# S6_Solenoid_Valve_Interlock.net
KiCad netlist of a schematic drawn in Altium Designer
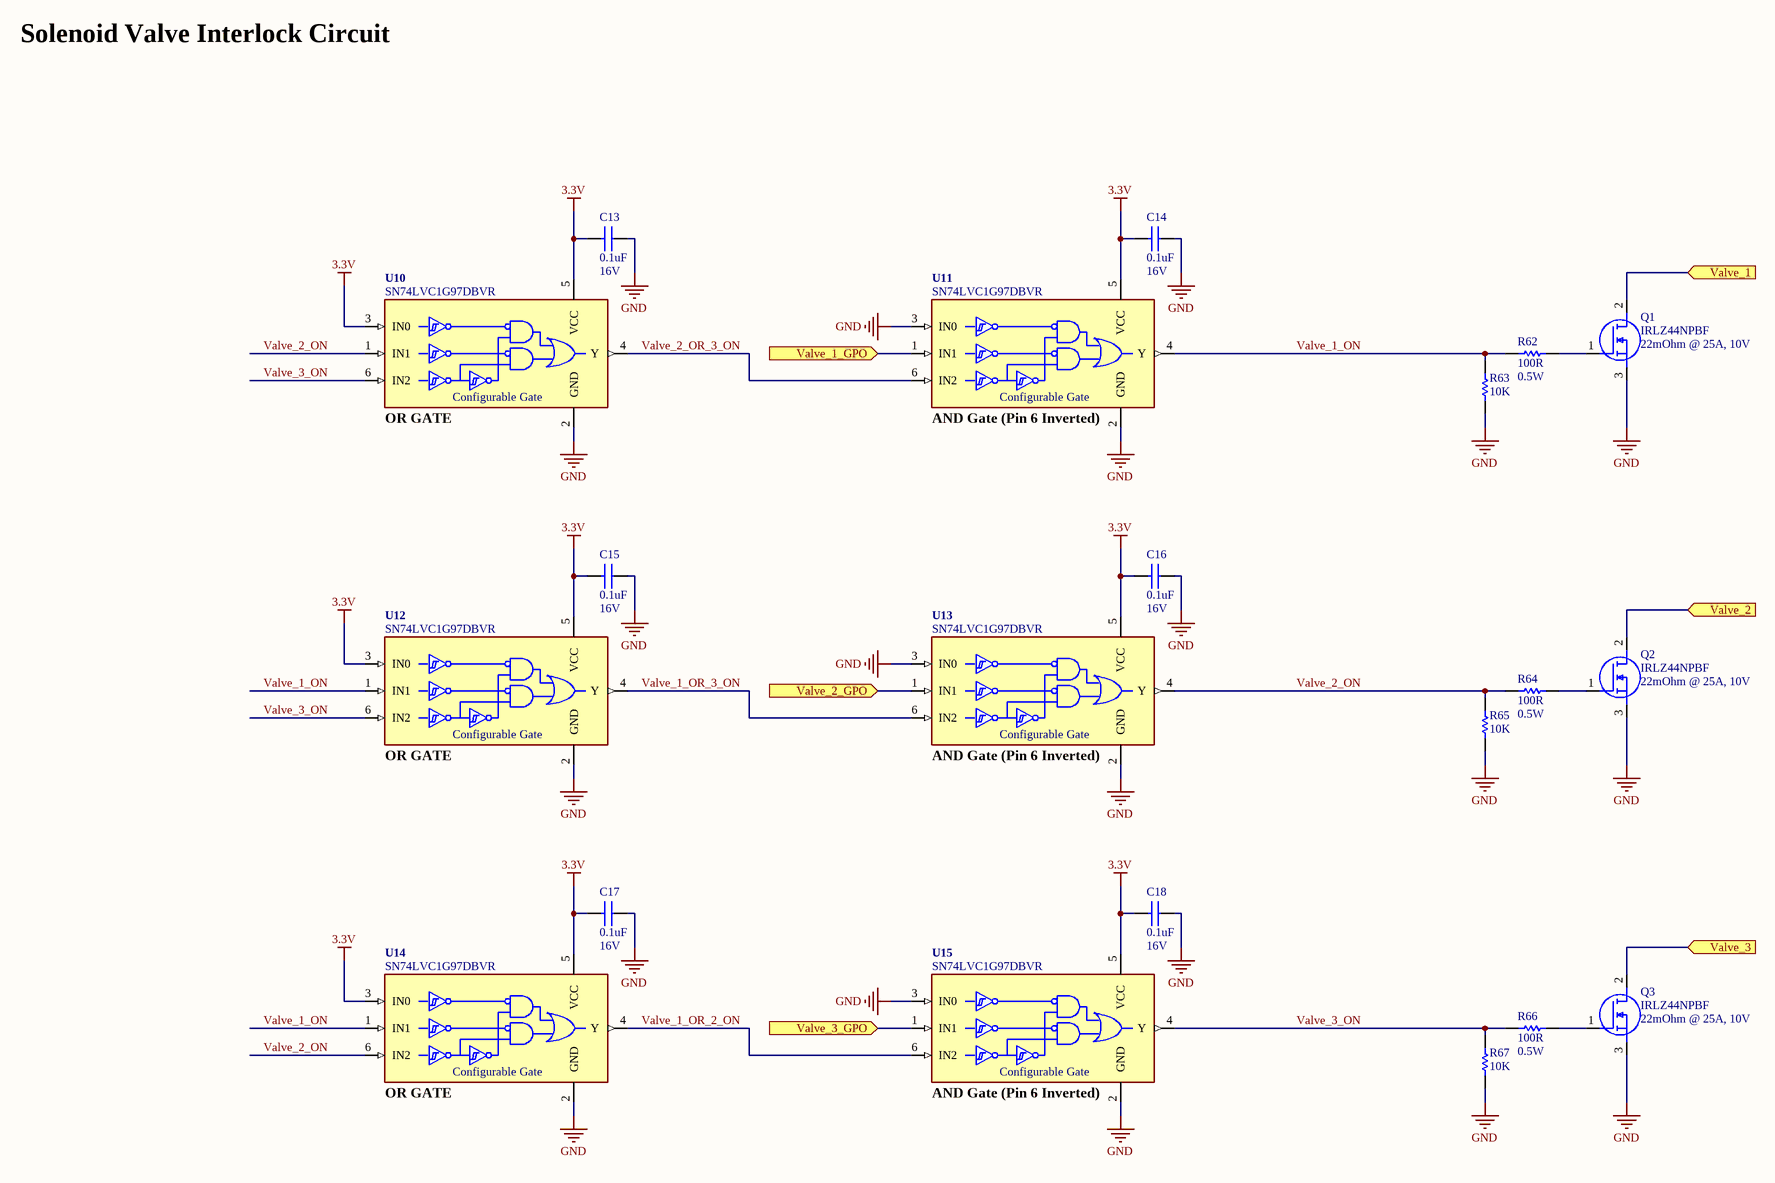
[diagram p0: S6_Solenoid_Valve_Interlock.SchDoc]

(export (version "E")
  (design (tool "Eeschema 10.0.6"))
  (components
    (comp (ref "C13")
      (value "0.1uF")
      (footprint "RWMN:CAPC1608X09N")
      (description "CAP CER 0.1UF 16V X7R 0603")
      (fields
        (field (name "MFG") "KEMET")
        (field (name "MFG_PART_NO") "C0603C104M4RACTU")
        (field (name "VOLTAGE") "16V")
      )
      (libsource (lib "AquaDrone") (part "CAP CER 0.1UF 16V X7R 0603"))
    )
    (comp (ref "C14")
      (value "0.1uF")
      (footprint "RWMN:CAPC1608X09N")
      (description "CAP CER 0.1UF 16V X7R 0603")
      (fields
        (field (name "MFG") "KEMET")
        (field (name "MFG_PART_NO") "C0603C104M4RACTU")
        (field (name "VOLTAGE") "16V")
      )
      (libsource (lib "AquaDrone") (part "CAP CER 0.1UF 16V X7R 0603"))
    )
    (comp (ref "C15")
      (value "0.1uF")
      (footprint "RWMN:CAPC1608X09N")
      (description "CAP CER 0.1UF 16V X7R 0603")
      (fields
        (field (name "MFG") "KEMET")
        (field (name "MFG_PART_NO") "C0603C104M4RACTU")
        (field (name "VOLTAGE") "16V")
      )
      (libsource (lib "AquaDrone") (part "CAP CER 0.1UF 16V X7R 0603"))
    )
    (comp (ref "C16")
      (value "0.1uF")
      (footprint "RWMN:CAPC1608X09N")
      (description "CAP CER 0.1UF 16V X7R 0603")
      (fields
        (field (name "MFG") "KEMET")
        (field (name "MFG_PART_NO") "C0603C104M4RACTU")
        (field (name "VOLTAGE") "16V")
      )
      (libsource (lib "AquaDrone") (part "CAP CER 0.1UF 16V X7R 0603"))
    )
    (comp (ref "C17")
      (value "0.1uF")
      (footprint "RWMN:CAPC1608X09N")
      (description "CAP CER 0.1UF 16V X7R 0603")
      (fields
        (field (name "MFG") "KEMET")
        (field (name "MFG_PART_NO") "C0603C104M4RACTU")
        (field (name "VOLTAGE") "16V")
      )
      (libsource (lib "AquaDrone") (part "CAP CER 0.1UF 16V X7R 0603"))
    )
    (comp (ref "C18")
      (value "0.1uF")
      (footprint "RWMN:CAPC1608X09N")
      (description "CAP CER 0.1UF 16V X7R 0603")
      (fields
        (field (name "MFG") "KEMET")
        (field (name "MFG_PART_NO") "C0603C104M4RACTU")
        (field (name "VOLTAGE") "16V")
      )
      (libsource (lib "AquaDrone") (part "CAP CER 0.1UF 16V X7R 0603"))
    )
    (comp (ref "Q1")
      (value "22mOhm @ 25A, 10V")
      (footprint "TO254P469X1042X1967-3P")
      (description "MOSFET N-CH 55V 47A TO-220AB")
      (fields (field (name "MFG") "Infineon Technologies") (field (name "MFG_PART_NO") "IRLZ44NPBF"))
      (libsource (lib "AquaDrone") (part "MOSFET N-CH 55V 47A TO-220AB"))
    )
    (comp (ref "Q2")
      (value "22mOhm @ 25A, 10V")
      (footprint "TO254P469X1042X1967-3P")
      (description "MOSFET N-CH 55V 47A TO-220AB")
      (fields (field (name "MFG") "Infineon Technologies") (field (name "MFG_PART_NO") "IRLZ44NPBF"))
      (libsource (lib "AquaDrone") (part "MOSFET N-CH 55V 47A TO-220AB"))
    )
    (comp (ref "Q3")
      (value "22mOhm @ 25A, 10V")
      (footprint "TO254P469X1042X1967-3P")
      (description "MOSFET N-CH 55V 47A TO-220AB")
      (fields (field (name "MFG") "Infineon Technologies") (field (name "MFG_PART_NO") "IRLZ44NPBF"))
      (libsource (lib "AquaDrone") (part "MOSFET N-CH 55V 47A TO-220AB"))
    )
    (comp (ref "R62")
      (value "100R")
      (footprint "RWMN:RESC3116X06N")
      (description "RES 100 OHM 1% 1/2W 1206")
      (fields
        (field (name "MFG") "Stackpole Electronics Inc")
        (field (name "MFG_PART_NO") "RNCP1206FTD100R")
        (field (name "POWER") "0.5W")
      )
      (libsource (lib "AquaDrone") (part "RES 100 OHM 1% 1/2W 1206"))
    )
    (comp (ref "R63")
      (value "10K")
      (footprint "RESC1608X06N")
      (description "RES SMD 10K OHM 1% 1/10W 0603")
      (fields (field (name "MFG") "Vishay Dale") (field (name "MFG_PART_NO") "CRCW060310K0FKEA"))
      (libsource (lib "AquaDrone") (part "RES SMD 10K OHM 1% 1/10W 0603"))
    )
    (comp (ref "R64")
      (value "100R")
      (footprint "RWMN:RESC3116X06N")
      (description "RES 100 OHM 1% 1/2W 1206")
      (fields
        (field (name "MFG") "Stackpole Electronics Inc")
        (field (name "MFG_PART_NO") "RNCP1206FTD100R")
        (field (name "POWER") "0.5W")
      )
      (libsource (lib "AquaDrone") (part "RES 100 OHM 1% 1/2W 1206"))
    )
    (comp (ref "R65")
      (value "10K")
      (footprint "RESC1608X06N")
      (description "RES SMD 10K OHM 1% 1/10W 0603")
      (fields (field (name "MFG") "Vishay Dale") (field (name "MFG_PART_NO") "CRCW060310K0FKEA"))
      (libsource (lib "AquaDrone") (part "RES SMD 10K OHM 1% 1/10W 0603"))
    )
    (comp (ref "R66")
      (value "100R")
      (footprint "RWMN:RESC3116X06N")
      (description "RES 100 OHM 1% 1/2W 1206")
      (fields
        (field (name "MFG") "Stackpole Electronics Inc")
        (field (name "MFG_PART_NO") "RNCP1206FTD100R")
        (field (name "POWER") "0.5W")
      )
      (libsource (lib "AquaDrone") (part "RES 100 OHM 1% 1/2W 1206"))
    )
    (comp (ref "R67")
      (value "10K")
      (footprint "RESC1608X06N")
      (description "RES SMD 10K OHM 1% 1/10W 0603")
      (fields (field (name "MFG") "Vishay Dale") (field (name "MFG_PART_NO") "CRCW060310K0FKEA"))
      (libsource (lib "AquaDrone") (part "RES SMD 10K OHM 1% 1/10W 0603"))
    )
    (comp (ref "U10")
      (value "SN74LVC1G97DBVR")
      (footprint "SOT65P210X110-6N_SN74LVC1G97DCK")
      (description "IC CONFIG MULT-FUNC GATE SOT23-6")
      (fields (field (name "MFG") "TI"))
      (libsource (lib "AquaDrone") (part "IC CONFIG MULT-FUNC GATE SOT23-6"))
    )
    (comp (ref "U11")
      (value "SN74LVC1G97DBVR")
      (footprint "SOT65P210X110-6N_SN74LVC1G97DCK")
      (description "IC CONFIG MULT-FUNC GATE SOT23-6")
      (fields (field (name "MFG") "TI"))
      (libsource (lib "AquaDrone") (part "IC CONFIG MULT-FUNC GATE SOT23-6"))
    )
    (comp (ref "U12")
      (value "SN74LVC1G97DBVR")
      (footprint "SOT65P210X110-6N_SN74LVC1G97DCK")
      (description "IC CONFIG MULT-FUNC GATE SOT23-6")
      (fields (field (name "MFG") "TI"))
      (libsource (lib "AquaDrone") (part "IC CONFIG MULT-FUNC GATE SOT23-6"))
    )
    (comp (ref "U13")
      (value "SN74LVC1G97DBVR")
      (footprint "SOT65P210X110-6N_SN74LVC1G97DCK")
      (description "IC CONFIG MULT-FUNC GATE SOT23-6")
      (fields (field (name "MFG") "TI"))
      (libsource (lib "AquaDrone") (part "IC CONFIG MULT-FUNC GATE SOT23-6"))
    )
    (comp (ref "U14")
      (value "SN74LVC1G97DBVR")
      (footprint "SOT65P210X110-6N_SN74LVC1G97DCK")
      (description "IC CONFIG MULT-FUNC GATE SOT23-6")
      (fields (field (name "MFG") "TI"))
      (libsource (lib "AquaDrone") (part "IC CONFIG MULT-FUNC GATE SOT23-6"))
    )
    (comp (ref "U15")
      (value "SN74LVC1G97DBVR")
      (footprint "SOT65P210X110-6N_SN74LVC1G97DCK")
      (description "IC CONFIG MULT-FUNC GATE SOT23-6")
      (fields (field (name "MFG") "TI"))
      (libsource (lib "AquaDrone") (part "IC CONFIG MULT-FUNC GATE SOT23-6"))
    )
  )
  (nets
    (net (code "1") (name "/Valve_1") (class "Default")
      (node (ref "Q1") (pin "2") (pinfunction "D_2") (pintype "passive"))
    )
    (net (code "2") (name "/Valve_1_GPO") (class "Default")
      (node (ref "U11") (pin "1") (pinfunction "IN1_1") (pintype "input"))
    )
    (net (code "3") (name "/Valve_1_ON") (class "Default")
      (node (ref "R62") (pin "1") (pinfunction "1_1") (pintype "passive"))
      (node (ref "R63") (pin "2") (pinfunction "2_2") (pintype "passive"))
      (node (ref "U11") (pin "4") (pinfunction "Y_4") (pintype "output"))
      (node (ref "U12") (pin "1") (pinfunction "IN1_1") (pintype "input"))
      (node (ref "U14") (pin "1") (pinfunction "IN1_1") (pintype "input"))
    )
    (net (code "4") (name "/Valve_1_OR_2_ON") (class "Default")
      (node (ref "U14") (pin "4") (pinfunction "Y_4") (pintype "output"))
      (node (ref "U15") (pin "6") (pinfunction "IN2_6") (pintype "input"))
    )
    (net (code "5") (name "/Valve_1_OR_3_ON") (class "Default")
      (node (ref "U12") (pin "4") (pinfunction "Y_4") (pintype "output"))
      (node (ref "U13") (pin "6") (pinfunction "IN2_6") (pintype "input"))
    )
    (net (code "6") (name "/Valve_2") (class "Default")
      (node (ref "Q2") (pin "2") (pinfunction "D_2") (pintype "passive"))
    )
    (net (code "7") (name "/Valve_2_GPO") (class "Default")
      (node (ref "U13") (pin "1") (pinfunction "IN1_1") (pintype "input"))
    )
    (net (code "8") (name "/Valve_2_ON") (class "Default")
      (node (ref "R64") (pin "1") (pinfunction "1_1") (pintype "passive"))
      (node (ref "R65") (pin "2") (pinfunction "2_2") (pintype "passive"))
      (node (ref "U10") (pin "1") (pinfunction "IN1_1") (pintype "input"))
      (node (ref "U13") (pin "4") (pinfunction "Y_4") (pintype "output"))
      (node (ref "U14") (pin "6") (pinfunction "IN2_6") (pintype "input"))
    )
    (net (code "9") (name "/Valve_2_OR_3_ON") (class "Default")
      (node (ref "U10") (pin "4") (pinfunction "Y_4") (pintype "output"))
      (node (ref "U11") (pin "6") (pinfunction "IN2_6") (pintype "input"))
    )
    (net (code "10") (name "/Valve_3") (class "Default")
      (node (ref "Q3") (pin "2") (pinfunction "D_2") (pintype "passive"))
    )
    (net (code "11") (name "/Valve_3_GPO") (class "Default")
      (node (ref "U15") (pin "1") (pinfunction "IN1_1") (pintype "input"))
    )
    (net (code "12") (name "/Valve_3_ON") (class "Default")
      (node (ref "R66") (pin "1") (pinfunction "1_1") (pintype "passive"))
      (node (ref "R67") (pin "2") (pinfunction "2_2") (pintype "passive"))
      (node (ref "U10") (pin "6") (pinfunction "IN2_6") (pintype "input"))
      (node (ref "U12") (pin "6") (pinfunction "IN2_6") (pintype "input"))
      (node (ref "U15") (pin "4") (pinfunction "Y_4") (pintype "output"))
    )
    (net (code "13") (name "3.3V") (class "Default")
      (node (ref "C13") (pin "2") (pinfunction "2_2") (pintype "passive"))
      (node (ref "C14") (pin "2") (pinfunction "2_2") (pintype "passive"))
      (node (ref "C15") (pin "2") (pinfunction "2_2") (pintype "passive"))
      (node (ref "C16") (pin "2") (pinfunction "2_2") (pintype "passive"))
      (node (ref "C17") (pin "2") (pinfunction "2_2") (pintype "passive"))
      (node (ref "C18") (pin "2") (pinfunction "2_2") (pintype "passive"))
      (node (ref "U10") (pin "3") (pinfunction "IN0_3") (pintype "input"))
      (node (ref "U10") (pin "5") (pinfunction "VCC_5") (pintype "power_in"))
      (node (ref "U11") (pin "5") (pinfunction "VCC_5") (pintype "power_in"))
      (node (ref "U12") (pin "3") (pinfunction "IN0_3") (pintype "input"))
      (node (ref "U12") (pin "5") (pinfunction "VCC_5") (pintype "power_in"))
      (node (ref "U13") (pin "5") (pinfunction "VCC_5") (pintype "power_in"))
      (node (ref "U14") (pin "3") (pinfunction "IN0_3") (pintype "input"))
      (node (ref "U14") (pin "5") (pinfunction "VCC_5") (pintype "power_in"))
      (node (ref "U15") (pin "5") (pinfunction "VCC_5") (pintype "power_in"))
    )
    (net (code "14") (name "GND") (class "Default")
      (node (ref "C13") (pin "1") (pinfunction "1_1") (pintype "passive"))
      (node (ref "C14") (pin "1") (pinfunction "1_1") (pintype "passive"))
      (node (ref "C15") (pin "1") (pinfunction "1_1") (pintype "passive"))
      (node (ref "C16") (pin "1") (pinfunction "1_1") (pintype "passive"))
      (node (ref "C17") (pin "1") (pinfunction "1_1") (pintype "passive"))
      (node (ref "C18") (pin "1") (pinfunction "1_1") (pintype "passive"))
      (node (ref "Q1") (pin "3") (pinfunction "S_3") (pintype "passive"))
      (node (ref "Q2") (pin "3") (pinfunction "S_3") (pintype "passive"))
      (node (ref "Q3") (pin "3") (pinfunction "S_3") (pintype "passive"))
      (node (ref "R63") (pin "1") (pinfunction "1_1") (pintype "passive"))
      (node (ref "R65") (pin "1") (pinfunction "1_1") (pintype "passive"))
      (node (ref "R67") (pin "1") (pinfunction "1_1") (pintype "passive"))
      (node (ref "U10") (pin "2") (pinfunction "GND_2") (pintype "power_in"))
      (node (ref "U11") (pin "2") (pinfunction "GND_2") (pintype "power_in"))
      (node (ref "U11") (pin "3") (pinfunction "IN0_3") (pintype "input"))
      (node (ref "U12") (pin "2") (pinfunction "GND_2") (pintype "power_in"))
      (node (ref "U13") (pin "2") (pinfunction "GND_2") (pintype "power_in"))
      (node (ref "U13") (pin "3") (pinfunction "IN0_3") (pintype "input"))
      (node (ref "U14") (pin "2") (pinfunction "GND_2") (pintype "power_in"))
      (node (ref "U15") (pin "2") (pinfunction "GND_2") (pintype "power_in"))
      (node (ref "U15") (pin "3") (pinfunction "IN0_3") (pintype "input"))
    )
    (net (code "15") (name "Net-(Q1-G)") (class "Default")
      (node (ref "Q1") (pin "1") (pinfunction "G_1") (pintype "passive"))
      (node (ref "R62") (pin "2") (pinfunction "2_2") (pintype "passive"))
    )
    (net (code "16") (name "Net-(Q2-G)") (class "Default")
      (node (ref "Q2") (pin "1") (pinfunction "G_1") (pintype "passive"))
      (node (ref "R64") (pin "2") (pinfunction "2_2") (pintype "passive"))
    )
    (net (code "17") (name "Net-(Q3-G)") (class "Default")
      (node (ref "Q3") (pin "1") (pinfunction "G_1") (pintype "passive"))
      (node (ref "R66") (pin "2") (pinfunction "2_2") (pintype "passive"))
    )
  )
)
